# linear_lm358.net
KiCad netlist of a schematic drawn in EAGLE
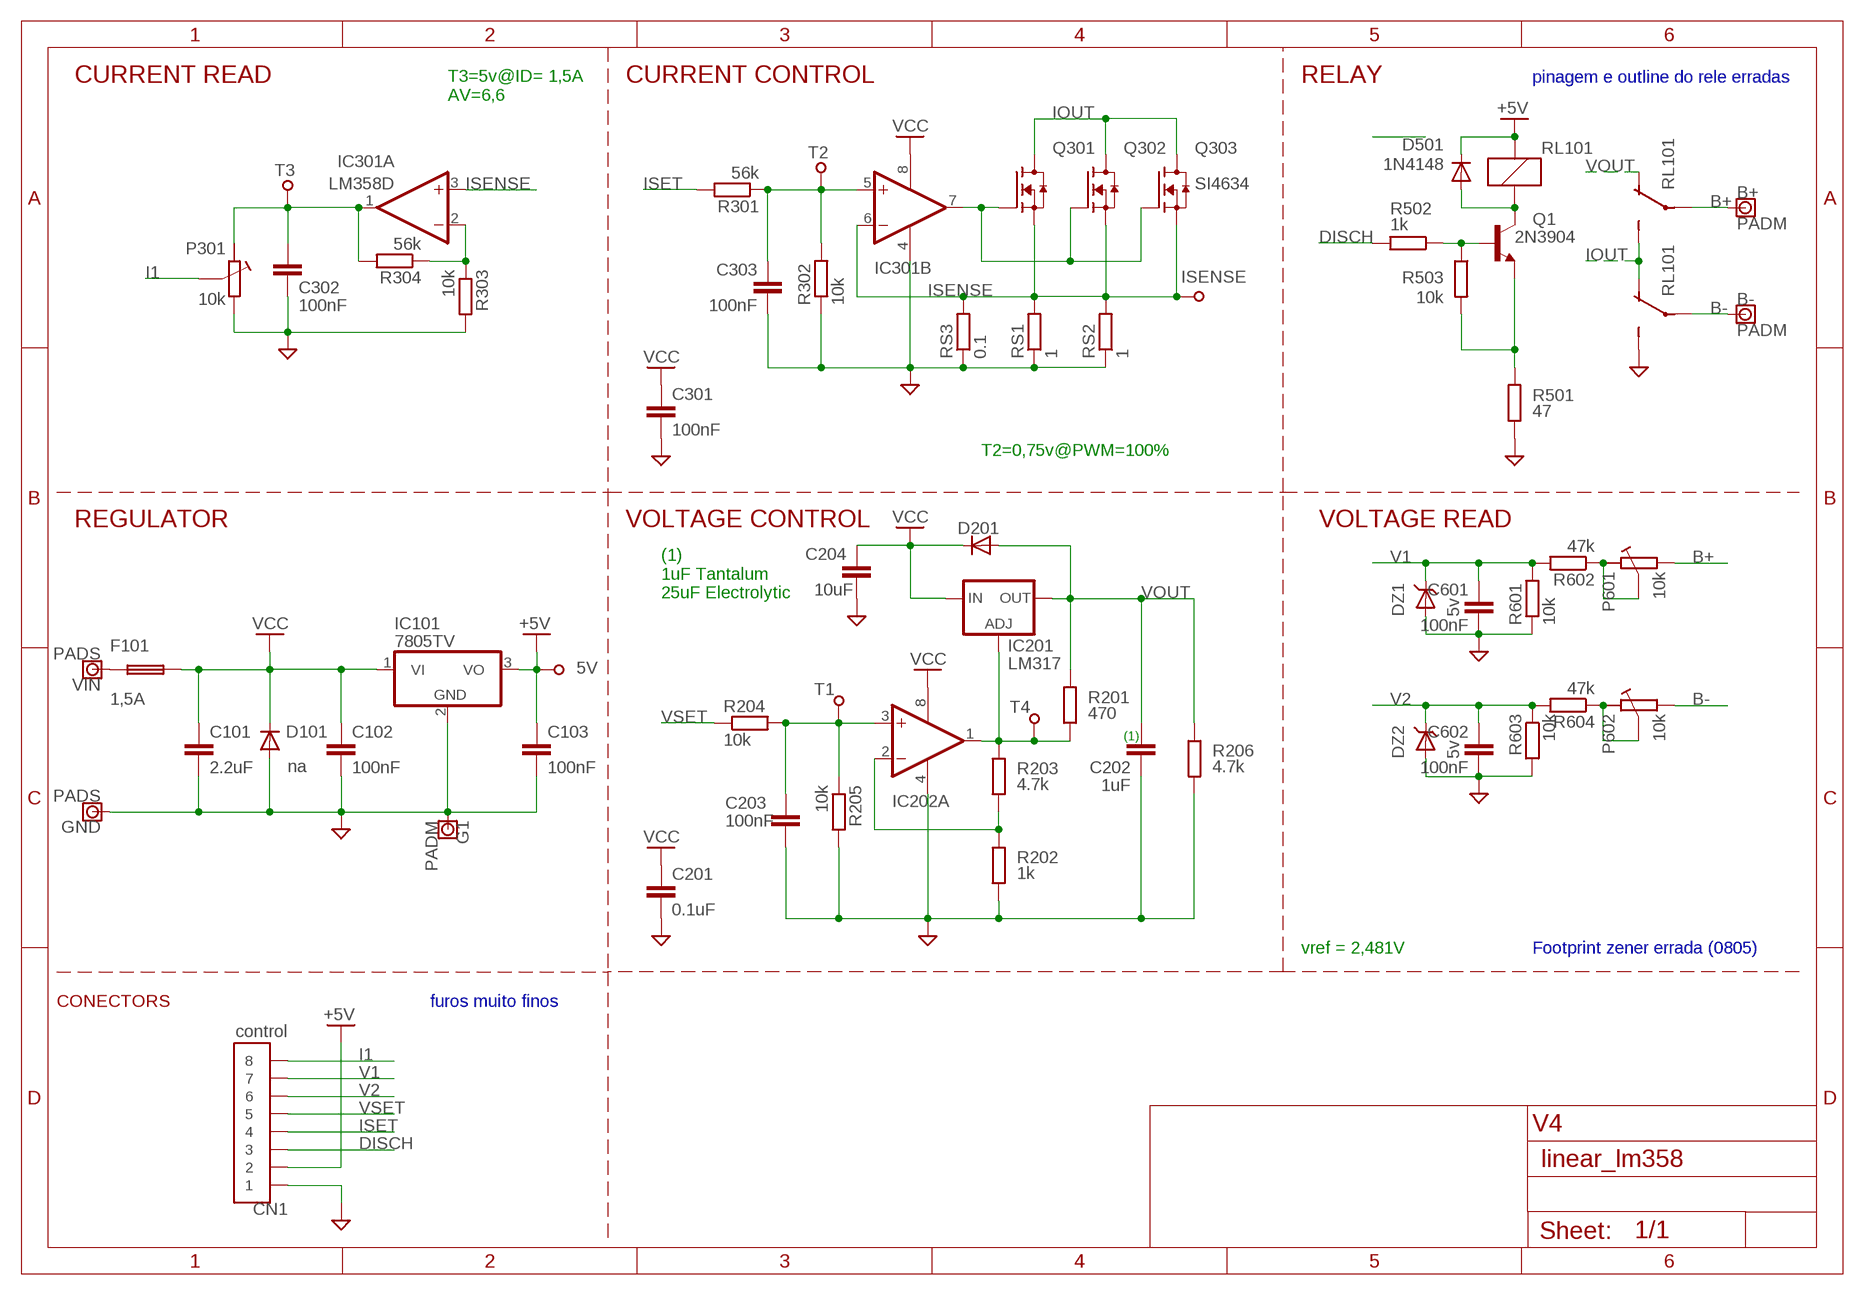
[diagram p0: schematic, sheet 1]

(export (version "E")
  (design (tool "Eeschema 10.0.6"))
  (components
    (comp (ref "5V")
      (value "TEST_POINT")
      (footprint "eagle-import:TP")
      (libsource (lib "eagle-import") (part "TEST_POINT"))
    )
    (comp (ref "B+")
      (value "PADM")
      (footprint "eagle-import:PAD_1M")
      (libsource (lib "eagle-import") (part "PADM"))
    )
    (comp (ref "B-")
      (value "PADM")
      (footprint "eagle-import:PAD_1M")
      (libsource (lib "eagle-import") (part "PADM"))
    )
    (comp (ref "C101")
      (value "2.2uF")
      (footprint "eagle-import:C3225")
      (libsource (lib "eagle-import") (part "C-EUC3225"))
    )
    (comp (ref "C102")
      (value "100nF")
      (footprint "eagle-import:C3225")
      (libsource (lib "eagle-import") (part "C-EUC3225"))
    )
    (comp (ref "C103")
      (value "100nF")
      (footprint "eagle-import:C3225")
      (libsource (lib "eagle-import") (part "C-EUC3225"))
    )
    (comp (ref "C201")
      (value "0.1uF")
      (footprint "eagle-import:C0805K")
      (libsource (lib "eagle-import") (part "C-EUC0805K"))
    )
    (comp (ref "C202")
      (value "1uF")
      (footprint "eagle-import:C1210")
      (libsource (lib "eagle-import") (part "C-EUC1210"))
    )
    (comp (ref "C203")
      (value "100nF")
      (footprint "eagle-import:C0805K")
      (libsource (lib "eagle-import") (part "C-EUC0805K"))
    )
    (comp (ref "C204")
      (value "10uF")
      (footprint "eagle-import:C1210")
      (libsource (lib "eagle-import") (part "C-EUC1210"))
    )
    (comp (ref "C301")
      (value "100nF")
      (footprint "eagle-import:C0805K")
      (libsource (lib "eagle-import") (part "C-EUC0805K"))
    )
    (comp (ref "C302")
      (value "100nF")
      (footprint "eagle-import:C0805K")
      (libsource (lib "eagle-import") (part "C-EUC0805K"))
    )
    (comp (ref "C303")
      (value "100nF")
      (footprint "eagle-import:C0805K")
      (libsource (lib "eagle-import") (part "C-EUC0805K"))
    )
    (comp (ref "C601")
      (value "100nF")
      (footprint "eagle-import:C0805K")
      (libsource (lib "eagle-import") (part "C-EUC0805K"))
    )
    (comp (ref "C602")
      (value "100nF")
      (footprint "eagle-import:C0805K")
      (libsource (lib "eagle-import") (part "C-EUC0805K"))
    )
    (comp (ref "CN1")
      (value "control")
      (footprint "eagle-import:SIL8-0.7")
      (libsource (lib "eagle-import") (part "CON80.7"))
    )
    (comp (ref "D101")
      (value "na")
      (footprint "eagle-import:DO214BA")
      (libsource (lib "eagle-import") (part "DIODE-DO214BA"))
    )
    (comp (ref "D201")
      (value "na")
      (footprint "eagle-import:DO214BA")
      (libsource (lib "eagle-import") (part "DIODE-DO214BA"))
    )
    (comp (ref "D501")
      (value "1N4148")
      (footprint "eagle-import:DO214BA")
      (libsource (lib "eagle-import") (part "DIODE-DO214BA"))
    )
    (comp (ref "DZ1")
      (value "5v")
      (footprint "eagle-import:D0805")
      (libsource (lib "eagle-import") (part "ZENER"))
    )
    (comp (ref "DZ2")
      (value "5v")
      (footprint "eagle-import:D0805")
      (libsource (lib "eagle-import") (part "ZENER"))
    )
    (comp (ref "F101")
      (value "1,5A")
      (footprint "eagle-import:F1210L")
      (libsource (lib "eagle-import") (part "FUSESMALLER_PADS"))
    )
    (comp (ref "G1")
      (value "PADM")
      (footprint "eagle-import:PAD_1M")
      (libsource (lib "eagle-import") (part "PADM"))
    )
    (comp (ref "GND")
      (value "PADS")
      (footprint "eagle-import:PAD_01")
      (libsource (lib "eagle-import") (part "PADS"))
    )
    (comp (ref "IC101")
      (value "7805TV")
      (footprint "eagle-import:TO220V")
      (libsource (lib "eagle-import") (part "78TV05"))
    )
    (comp (ref "IC201")
      (value "LM317")
      (footprint "eagle-import:317TS")
      (libsource (lib "eagle-import") (part "LM317TS"))
    )
    (comp (ref "IC202")
      (value "LM358D")
      (footprint "eagle-import:SO08")
      (libsource (lib "eagle-import") (part "LM358D"))
    )
    (comp (ref "IC301")
      (value "LM358D")
      (footprint "eagle-import:SO08")
      (libsource (lib "eagle-import") (part "LM358D"))
    )
    (comp (ref "ISENSE")
      (value "TEST_POINT")
      (footprint "eagle-import:TP")
      (libsource (lib "eagle-import") (part "TEST_POINT"))
    )
    (comp (ref "P301")
      (value "10k")
      (footprint "eagle-import:TRIM_POT")
      (libsource (lib "eagle-import") (part "POT"))
    )
    (comp (ref "P601")
      (value "10k")
      (footprint "eagle-import:TRIM_POT")
      (libsource (lib "eagle-import") (part "POT"))
    )
    (comp (ref "P602")
      (value "10k")
      (footprint "eagle-import:TRIM_POT")
      (libsource (lib "eagle-import") (part "POT"))
    )
    (comp (ref "Q1")
      (value "2N3904")
      (footprint "eagle-import:SOT23")
      (libsource (lib "eagle-import") (part "2N3904"))
    )
    (comp (ref "Q301")
      (value "AO4468")
      (footprint "eagle-import:SO-8")
      (libsource (lib "eagle-import") (part "AO4468"))
    )
    (comp (ref "Q302")
      (value "AO4468")
      (footprint "eagle-import:SO-8")
      (libsource (lib "eagle-import") (part "AO4468"))
    )
    (comp (ref "Q303")
      (value "SI4634")
      (footprint "eagle-import:SO-8")
      (libsource (lib "eagle-import") (part "AO4468"))
    )
    (comp (ref "R201")
      (value "470")
      (footprint "eagle-import:M0805")
      (libsource (lib "eagle-import") (part "R-EU_M0805"))
    )
    (comp (ref "R202")
      (value "1k")
      (footprint "eagle-import:M0805")
      (libsource (lib "eagle-import") (part "R-EU_M0805"))
    )
    (comp (ref "R203")
      (value "4.7k")
      (footprint "eagle-import:M0805")
      (libsource (lib "eagle-import") (part "R-EU_M0805"))
    )
    (comp (ref "R204")
      (value "10k")
      (footprint "eagle-import:M0805")
      (libsource (lib "eagle-import") (part "R-EU_M0805"))
    )
    (comp (ref "R205")
      (value "10k")
      (footprint "eagle-import:M0805")
      (libsource (lib "eagle-import") (part "R-EU_M0805"))
    )
    (comp (ref "R206")
      (value "4.7k")
      (footprint "eagle-import:M0805")
      (libsource (lib "eagle-import") (part "R-EU_M0805"))
    )
    (comp (ref "R301")
      (value "56k")
      (footprint "eagle-import:M0805")
      (libsource (lib "eagle-import") (part "R-EU_M0805"))
    )
    (comp (ref "R302")
      (value "10k")
      (footprint "eagle-import:M0805")
      (libsource (lib "eagle-import") (part "R-EU_M0805"))
    )
    (comp (ref "R303")
      (value "10k")
      (footprint "eagle-import:M0805")
      (libsource (lib "eagle-import") (part "R-EU_M0805"))
    )
    (comp (ref "R304")
      (value "56k")
      (footprint "eagle-import:M0805")
      (libsource (lib "eagle-import") (part "R-EU_M0805"))
    )
    (comp (ref "R501")
      (value "47")
      (footprint "eagle-import:R0603")
      (libsource (lib "eagle-import") (part "R-EU_R0603"))
    )
    (comp (ref "R502")
      (value "1k")
      (footprint "eagle-import:R0603")
      (libsource (lib "eagle-import") (part "R-EU_R0603"))
    )
    (comp (ref "R503")
      (value "10k")
      (footprint "eagle-import:R0603")
      (libsource (lib "eagle-import") (part "R-EU_R0603"))
    )
    (comp (ref "R601")
      (value "10k")
      (footprint "eagle-import:M0805")
      (libsource (lib "eagle-import") (part "R-EU_M0805"))
    )
    (comp (ref "R602")
      (value "47k")
      (footprint "eagle-import:M0805")
      (libsource (lib "eagle-import") (part "R-EU_M0805"))
    )
    (comp (ref "R603")
      (value "10k")
      (footprint "eagle-import:M0805")
      (libsource (lib "eagle-import") (part "R-EU_M0805"))
    )
    (comp (ref "R604")
      (value "47k")
      (footprint "eagle-import:M0805")
      (libsource (lib "eagle-import") (part "R-EU_M0805"))
    )
    (comp (ref "RL101")
      (value "RELAY_351S")
      (footprint "eagle-import:351S")
      (libsource (lib "eagle-import") (part "RELAY_351S"))
    )
    (comp (ref "RS1")
      (value "1")
      (footprint "eagle-import:0617_17")
      (libsource (lib "eagle-import") (part "R-EU_0617/17"))
    )
    (comp (ref "RS2")
      (value "1")
      (footprint "eagle-import:0617_17")
      (libsource (lib "eagle-import") (part "R-EU_0617/17"))
    )
    (comp (ref "RS3")
      (value "0.1")
      (footprint "eagle-import:R2512")
      (libsource (lib "eagle-import") (part "R-EU_R2512"))
    )
    (comp (ref "T1")
      (value "TEST_POINT")
      (footprint "eagle-import:TP")
      (libsource (lib "eagle-import") (part "TEST_POINT"))
    )
    (comp (ref "T2")
      (value "TEST_POINT")
      (footprint "eagle-import:TP")
      (libsource (lib "eagle-import") (part "TEST_POINT"))
    )
    (comp (ref "T3")
      (value "TEST_POINT")
      (footprint "eagle-import:TP")
      (libsource (lib "eagle-import") (part "TEST_POINT"))
    )
    (comp (ref "T4")
      (value "TEST_POINT")
      (footprint "eagle-import:TP")
      (libsource (lib "eagle-import") (part "TEST_POINT"))
    )
    (comp (ref "VIN")
      (value "PADS")
      (footprint "eagle-import:PAD_01")
      (libsource (lib "eagle-import") (part "PADS"))
    )
  )
  (nets
    (net (code "1") (name "+5V") (class "Default")
      (node (ref "5V") (pin "1") (pinfunction "P$1_1") (pintype "bidirectional"))
      (node (ref "C103") (pin "1") (pinfunction "1_1") (pintype "passive"))
      (node (ref "CN1") (pin "2") (pinfunction "2_2") (pintype "bidirectional"))
      (node (ref "D501") (pin "C") (pinfunction "C_C") (pintype "passive"))
      (node (ref "IC101") (pin "3") (pinfunction "VO_3") (pintype "passive"))
      (node (ref "RL101") (pin "C1") (pinfunction "1_C1") (pintype "passive"))
    )
    (net (code "2") (name "/B+") (class "Default")
      (node (ref "B+") (pin "1") (pinfunction "P_1") (pintype "bidirectional"))
      (node (ref "P601") (pin "3") (pinfunction "3_3") (pintype "passive"))
      (node (ref "RL101") (pin "P1") (pinfunction "P_P1") (pintype "passive"))
    )
    (net (code "3") (name "/B-") (class "Default")
      (node (ref "B-") (pin "1") (pinfunction "P_1") (pintype "bidirectional"))
      (node (ref "P602") (pin "3") (pinfunction "3_3") (pintype "passive"))
      (node (ref "RL101") (pin "P2") (pinfunction "P_P2") (pintype "passive"))
    )
    (net (code "4") (name "/DISCH") (class "Default")
      (node (ref "CN1") (pin "3") (pinfunction "3_3") (pintype "bidirectional"))
      (node (ref "R502") (pin "2") (pinfunction "2_2") (pintype "passive"))
    )
    (net (code "5") (name "/I1") (class "Default")
      (node (ref "CN1") (pin "8") (pinfunction "8_8") (pintype "bidirectional"))
      (node (ref "P301") (pin "2") (pinfunction "2_2") (pintype "passive"))
    )
    (net (code "6") (name "/IOUT") (class "Default")
      (node (ref "Q301") (pin "5") (pinfunction "D_5") (pintype "passive"))
      (node (ref "Q301") (pin "6") (pinfunction "D_6") (pintype "passive"))
      (node (ref "Q301") (pin "7") (pinfunction "D_7") (pintype "passive"))
      (node (ref "Q301") (pin "8") (pinfunction "D_8") (pintype "passive"))
      (node (ref "Q302") (pin "5") (pinfunction "D_5") (pintype "passive"))
      (node (ref "Q302") (pin "6") (pinfunction "D_6") (pintype "passive"))
      (node (ref "Q302") (pin "7") (pinfunction "D_7") (pintype "passive"))
      (node (ref "Q302") (pin "8") (pinfunction "D_8") (pintype "passive"))
      (node (ref "Q303") (pin "5") (pinfunction "D_5") (pintype "passive"))
      (node (ref "Q303") (pin "6") (pinfunction "D_6") (pintype "passive"))
      (node (ref "Q303") (pin "7") (pinfunction "D_7") (pintype "passive"))
      (node (ref "Q303") (pin "8") (pinfunction "D_8") (pintype "passive"))
      (node (ref "RL101") (pin "NC2") (pinfunction "NC_NC2") (pintype "passive"))
      (node (ref "RL101") (pin "NO1") (pinfunction "NO_NO1") (pintype "passive"))
    )
    (net (code "7") (name "/ISENSE") (class "Default")
      (node (ref "IC301") (pin "3") (pinfunction "+IN_3") (pintype "input"))
      (node (ref "IC301") (pin "6") (pinfunction "-IN_6") (pintype "input"))
      (node (ref "ISENSE") (pin "1") (pinfunction "P$1_1") (pintype "bidirectional"))
      (node (ref "Q301") (pin "1") (pinfunction "S_1") (pintype "passive"))
      (node (ref "Q301") (pin "2") (pinfunction "S_2") (pintype "passive"))
      (node (ref "Q301") (pin "3") (pinfunction "S_3") (pintype "passive"))
      (node (ref "Q302") (pin "1") (pinfunction "S_1") (pintype "passive"))
      (node (ref "Q302") (pin "2") (pinfunction "S_2") (pintype "passive"))
      (node (ref "Q302") (pin "3") (pinfunction "S_3") (pintype "passive"))
      (node (ref "Q303") (pin "1") (pinfunction "S_1") (pintype "passive"))
      (node (ref "Q303") (pin "2") (pinfunction "S_2") (pintype "passive"))
      (node (ref "Q303") (pin "3") (pinfunction "S_3") (pintype "passive"))
      (node (ref "RS1") (pin "2") (pinfunction "2_2") (pintype "passive"))
      (node (ref "RS2") (pin "2") (pinfunction "2_2") (pintype "passive"))
      (node (ref "RS3") (pin "2") (pinfunction "2_2") (pintype "passive"))
    )
    (net (code "8") (name "/ISET") (class "Default")
      (node (ref "CN1") (pin "4") (pinfunction "4_4") (pintype "bidirectional"))
      (node (ref "R301") (pin "2") (pinfunction "2_2") (pintype "passive"))
    )
    (net (code "9") (name "/V1") (class "Default")
      (node (ref "C601") (pin "1") (pinfunction "1_1") (pintype "passive"))
      (node (ref "CN1") (pin "7") (pinfunction "7_7") (pintype "bidirectional"))
      (node (ref "DZ1") (pin "K") (pinfunction "C_K") (pintype "passive"))
      (node (ref "R601") (pin "2") (pinfunction "2_2") (pintype "passive"))
      (node (ref "R602") (pin "2") (pinfunction "2_2") (pintype "passive"))
    )
    (net (code "10") (name "/V2") (class "Default")
      (node (ref "C602") (pin "1") (pinfunction "1_1") (pintype "passive"))
      (node (ref "CN1") (pin "6") (pinfunction "6_6") (pintype "bidirectional"))
      (node (ref "DZ2") (pin "K") (pinfunction "C_K") (pintype "passive"))
      (node (ref "R603") (pin "1") (pinfunction "1_1") (pintype "passive"))
      (node (ref "R604") (pin "2") (pinfunction "2_2") (pintype "passive"))
    )
    (net (code "11") (name "/VOUT") (class "Default")
      (node (ref "C202") (pin "1") (pinfunction "1_1") (pintype "passive"))
      (node (ref "D201") (pin "A") (pinfunction "A_A") (pintype "passive"))
      (node (ref "IC201") (pin "2") (pinfunction "OUT_2") (pintype "passive"))
      (node (ref "R201") (pin "2") (pinfunction "2_2") (pintype "passive"))
      (node (ref "R206") (pin "1") (pinfunction "1_1") (pintype "passive"))
      (node (ref "RL101") (pin "NC1") (pinfunction "NC_NC1") (pintype "passive"))
    )
    (net (code "12") (name "/VSET") (class "Default")
      (node (ref "CN1") (pin "5") (pinfunction "5_5") (pintype "bidirectional"))
      (node (ref "R204") (pin "1") (pinfunction "1_1") (pintype "passive"))
    )
    (net (code "13") (name "GND") (class "Default")
      (node (ref "C101") (pin "2") (pinfunction "2_2") (pintype "passive"))
      (node (ref "C102") (pin "2") (pinfunction "2_2") (pintype "passive"))
      (node (ref "C103") (pin "2") (pinfunction "2_2") (pintype "passive"))
      (node (ref "C201") (pin "2") (pinfunction "2_2") (pintype "passive"))
      (node (ref "C202") (pin "2") (pinfunction "2_2") (pintype "passive"))
      (node (ref "C203") (pin "2") (pinfunction "2_2") (pintype "passive"))
      (node (ref "C204") (pin "2") (pinfunction "2_2") (pintype "passive"))
      (node (ref "C301") (pin "2") (pinfunction "2_2") (pintype "passive"))
      (node (ref "C302") (pin "1") (pinfunction "1_1") (pintype "passive"))
      (node (ref "C303") (pin "1") (pinfunction "1_1") (pintype "passive"))
      (node (ref "C601") (pin "2") (pinfunction "2_2") (pintype "passive"))
      (node (ref "C602") (pin "2") (pinfunction "2_2") (pintype "passive"))
      (node (ref "CN1") (pin "1") (pinfunction "1_1") (pintype "bidirectional"))
      (node (ref "D101") (pin "A") (pinfunction "A_A") (pintype "passive"))
      (node (ref "DZ1") (pin "A") (pinfunction "A_A") (pintype "passive"))
      (node (ref "DZ2") (pin "A") (pinfunction "A_A") (pintype "passive"))
      (node (ref "G1") (pin "1") (pinfunction "P_1") (pintype "bidirectional"))
      (node (ref "GND") (pin "P") (pinfunction "P_P") (pintype "bidirectional"))
      (node (ref "IC101") (pin "2") (pinfunction "GND_2") (pintype "passive"))
      (node (ref "IC202") (pin "4") (pinfunction "V-_4") (pintype "power_in"))
      (node (ref "IC301") (pin "4") (pinfunction "V-_4") (pintype "power_in"))
      (node (ref "P301") (pin "3") (pinfunction "3_3") (pintype "passive"))
      (node (ref "R202") (pin "2") (pinfunction "2_2") (pintype "passive"))
      (node (ref "R205") (pin "2") (pinfunction "2_2") (pintype "passive"))
      (node (ref "R206") (pin "2") (pinfunction "2_2") (pintype "passive"))
      (node (ref "R302") (pin "1") (pinfunction "1_1") (pintype "passive"))
      (node (ref "R303") (pin "2") (pinfunction "2_2") (pintype "passive"))
      (node (ref "R501") (pin "1") (pinfunction "1_1") (pintype "passive"))
      (node (ref "R601") (pin "1") (pinfunction "1_1") (pintype "passive"))
      (node (ref "R603") (pin "2") (pinfunction "2_2") (pintype "passive"))
      (node (ref "RL101") (pin "NO2") (pinfunction "NO_NO2") (pintype "passive"))
      (node (ref "RS1") (pin "1") (pinfunction "1_1") (pintype "passive"))
      (node (ref "RS2") (pin "1") (pinfunction "1_1") (pintype "passive"))
      (node (ref "RS3") (pin "1") (pinfunction "1_1") (pintype "passive"))
    )
    (net (code "14") (name "Net-(F101-Pad1)") (class "Default")
      (node (ref "F101") (pin "1") (pinfunction "1_1") (pintype "bidirectional"))
      (node (ref "VIN") (pin "P") (pinfunction "P_P") (pintype "bidirectional"))
    )
    (net (code "15") (name "Net-(IC201-ADJ)") (class "Default")
      (node (ref "IC201") (pin "1") (pinfunction "ADJ_1") (pintype "input"))
      (node (ref "IC202") (pin "1") (pinfunction "OUT_1") (pintype "output"))
      (node (ref "R201") (pin "1") (pinfunction "1_1") (pintype "passive"))
      (node (ref "R203") (pin "1") (pinfunction "1_1") (pintype "passive"))
      (node (ref "T4") (pin "1") (pinfunction "P$1_1") (pintype "bidirectional"))
    )
    (net (code "16") (name "Net-(IC202A-+IN)") (class "Default")
      (node (ref "C203") (pin "1") (pinfunction "1_1") (pintype "passive"))
      (node (ref "IC202") (pin "3") (pinfunction "+IN_3") (pintype "input"))
      (node (ref "R204") (pin "2") (pinfunction "2_2") (pintype "passive"))
      (node (ref "R205") (pin "1") (pinfunction "1_1") (pintype "passive"))
      (node (ref "T1") (pin "1") (pinfunction "P$1_1") (pintype "bidirectional"))
    )
    (net (code "17") (name "Net-(IC202A--IN)") (class "Default")
      (node (ref "IC202") (pin "2") (pinfunction "-IN_2") (pintype "input"))
      (node (ref "R202") (pin "1") (pinfunction "1_1") (pintype "passive"))
      (node (ref "R203") (pin "2") (pinfunction "2_2") (pintype "passive"))
    )
    (net (code "18") (name "Net-(IC301A--IN)") (class "Default")
      (node (ref "IC301") (pin "2") (pinfunction "-IN_2") (pintype "input"))
      (node (ref "R303") (pin "1") (pinfunction "1_1") (pintype "passive"))
      (node (ref "R304") (pin "1") (pinfunction "1_1") (pintype "passive"))
    )
    (net (code "19") (name "Net-(IC301A-OUT)") (class "Default")
      (node (ref "C302") (pin "2") (pinfunction "2_2") (pintype "passive"))
      (node (ref "IC301") (pin "1") (pinfunction "OUT_1") (pintype "output"))
      (node (ref "P301") (pin "1") (pinfunction "1_1") (pintype "passive"))
      (node (ref "R304") (pin "2") (pinfunction "2_2") (pintype "passive"))
      (node (ref "T3") (pin "1") (pinfunction "P$1_1") (pintype "bidirectional"))
    )
    (net (code "20") (name "Net-(IC301B-+IN)") (class "Default")
      (node (ref "C303") (pin "2") (pinfunction "2_2") (pintype "passive"))
      (node (ref "IC301") (pin "5") (pinfunction "+IN_5") (pintype "input"))
      (node (ref "R301") (pin "1") (pinfunction "1_1") (pintype "passive"))
      (node (ref "R302") (pin "2") (pinfunction "2_2") (pintype "passive"))
      (node (ref "T2") (pin "1") (pinfunction "P$1_1") (pintype "bidirectional"))
    )
    (net (code "21") (name "Net-(IC301B-OUT)") (class "Default")
      (node (ref "IC301") (pin "7") (pinfunction "OUT_7") (pintype "output"))
      (node (ref "Q301") (pin "4") (pinfunction "G_4") (pintype "passive"))
      (node (ref "Q302") (pin "4") (pinfunction "G_4") (pintype "passive"))
      (node (ref "Q303") (pin "4") (pinfunction "G_4") (pintype "passive"))
    )
    (net (code "22") (name "Net-(P601-Pad1)") (class "Default")
      (node (ref "P601") (pin "1") (pinfunction "1_1") (pintype "passive"))
      (node (ref "P601") (pin "2") (pinfunction "2_2") (pintype "passive"))
      (node (ref "R602") (pin "1") (pinfunction "1_1") (pintype "passive"))
    )
    (net (code "23") (name "Net-(P602-Pad1)") (class "Default")
      (node (ref "P602") (pin "1") (pinfunction "1_1") (pintype "passive"))
      (node (ref "P602") (pin "2") (pinfunction "2_2") (pintype "passive"))
      (node (ref "R604") (pin "1") (pinfunction "1_1") (pintype "passive"))
    )
    (net (code "24") (name "Net-(Q1-B)") (class "Default")
      (node (ref "Q1") (pin "1") (pinfunction "B_1") (pintype "passive"))
      (node (ref "R502") (pin "1") (pinfunction "1_1") (pintype "passive"))
      (node (ref "R503") (pin "1") (pinfunction "1_1") (pintype "passive"))
    )
    (net (code "25") (name "Net-(Q1-C)") (class "Default")
      (node (ref "D501") (pin "A") (pinfunction "A_A") (pintype "passive"))
      (node (ref "Q1") (pin "3") (pinfunction "C_3") (pintype "passive"))
      (node (ref "RL101") (pin "C2") (pinfunction "2_C2") (pintype "passive"))
    )
    (net (code "26") (name "Net-(Q1-E)") (class "Default")
      (node (ref "Q1") (pin "2") (pinfunction "E_2") (pintype "passive"))
      (node (ref "R501") (pin "2") (pinfunction "2_2") (pintype "passive"))
      (node (ref "R503") (pin "2") (pinfunction "2_2") (pintype "passive"))
    )
    (net (code "27") (name "VCC") (class "Default")
      (node (ref "C101") (pin "1") (pinfunction "1_1") (pintype "passive"))
      (node (ref "C102") (pin "1") (pinfunction "1_1") (pintype "passive"))
      (node (ref "C201") (pin "1") (pinfunction "1_1") (pintype "passive"))
      (node (ref "C204") (pin "1") (pinfunction "1_1") (pintype "passive"))
      (node (ref "C301") (pin "1") (pinfunction "1_1") (pintype "passive"))
      (node (ref "D101") (pin "C") (pinfunction "C_C") (pintype "passive"))
      (node (ref "D201") (pin "C") (pinfunction "C_C") (pintype "passive"))
      (node (ref "F101") (pin "2") (pinfunction "2_2") (pintype "bidirectional"))
      (node (ref "IC101") (pin "1") (pinfunction "VI_1") (pintype "input"))
      (node (ref "IC201") (pin "3") (pinfunction "IN_3") (pintype "input"))
      (node (ref "IC202") (pin "8") (pinfunction "V+_8") (pintype "power_in"))
      (node (ref "IC301") (pin "8") (pinfunction "V+_8") (pintype "power_in"))
    )
  )
)
